# DRLGabarit.net
KiCad netlist of a schematic drawn in Altium Designer
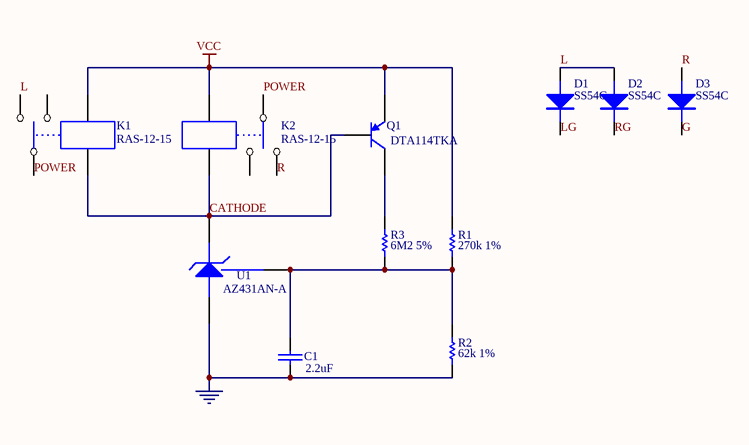
[diagram p0: DRLGabarit.SchDoc]

(export (version "E")
  (design (tool "Eeschema 10.0.6"))
  (components
    (comp (ref "C1")
      (value "2.2uF")
      (footprint "0805")
      (description "Capacitor")
      (libsource (lib "*") (part "CAP"))
    )
    (comp (ref "D1")
      (value "SS54C")
      (footprint "SMC")
      (description "Diode")
      (libsource (lib "Miscellaneous Devices") (part "DIODE"))
    )
    (comp (ref "D2")
      (value "SS54C")
      (footprint "SMC")
      (description "Diode")
      (libsource (lib "Miscellaneous Devices") (part "DIODE"))
    )
    (comp (ref "D3")
      (value "SS54C")
      (footprint "SMC")
      (description "Diode")
      (libsource (lib "Miscellaneous Devices") (part "DIODE"))
    )
    (comp (ref "K1")
      (value "RAS-12-15")
      (footprint "RELAY5PIN")
      (libsource (lib "Miscellaneous Devices") (part "RELAY-SPDT"))
    )
    (comp (ref "K2")
      (value "RAS-12-15")
      (footprint "RELAY5PIN")
      (libsource (lib "Miscellaneous Devices") (part "RELAY-SPDT"))
    )
    (comp (ref "Q1")
      (value "DTA114TKA")
      (footprint "sot-23")
      (description "PNP Bipolar Transistor")
      (fields
        (field (name "MANUFACTURER") "Generic Components")
        (field (name "PUBLISHER") "Altium Hobart Technology Centre")
      )
      (libsource (lib "Miscellaneous Devices") (part "PNP"))
    )
    (comp (ref "R1")
      (value "270k 1%")
      (footprint "0805")
      (description "Resistor")
      (fields
        (field (name "MANUFACTURER") "Generic Components")
        (field (name "PUBLISHER") "Altium Hobart Technology Centre")
      )
      (libsource (lib "Miscellaneous Devices") (part "Res1"))
    )
    (comp (ref "R2")
      (value "62k 1%")
      (footprint "0805")
      (description "Resistor")
      (fields
        (field (name "MANUFACTURER") "Generic Components")
        (field (name "PUBLISHER") "Altium Hobart Technology Centre")
      )
      (libsource (lib "Miscellaneous Devices") (part "Res1"))
    )
    (comp (ref "R3")
      (value "6M2 5%")
      (footprint "0805")
      (description "Resistor")
      (fields
        (field (name "MANUFACTURER") "Generic Components")
        (field (name "PUBLISHER") "Altium Hobart Technology Centre")
      )
      (libsource (lib "Miscellaneous Devices") (part "Res1"))
    )
    (comp (ref "U1") (value "AZ431AN-A") (footprint "SOT-23") (libsource (lib "Devices") (part "TL431")))
  )
  (nets
    (net (code "1") (name "/CATHODE") (class "Default")
      (node (ref "K1") (pin "4") (pinfunction "4_4") (pintype "passive"))
      (node (ref "K2") (pin "5") (pinfunction "5_5") (pintype "passive"))
      (node (ref "Q1") (pin "1") (pinfunction "B_1") (pintype "passive"))
      (node (ref "U1") (pin "3") (pinfunction "K_3") (pintype "passive"))
    )
    (net (code "2") (name "/G") (class "Default")
      (node (ref "D3") (pin "1") (pinfunction "K_1") (pintype "passive"))
    )
    (net (code "3") (name "/L") (class "Default")
      (node (ref "D1") (pin "2") (pinfunction "A_2") (pintype "passive"))
      (node (ref "D2") (pin "2") (pinfunction "A_2") (pintype "passive"))
      (node (ref "K1") (pin "2") (pinfunction "2_2") (pintype "passive"))
    )
    (net (code "4") (name "/LG") (class "Default")
      (node (ref "D1") (pin "1") (pinfunction "K_1") (pintype "passive"))
    )
    (net (code "5") (name "/POWER") (class "Default")
      (node (ref "K1") (pin "1") (pinfunction "1_1") (pintype "passive"))
      (node (ref "K2") (pin "1") (pinfunction "1_1") (pintype "passive"))
    )
    (net (code "6") (name "/R") (class "Default")
      (node (ref "D3") (pin "2") (pinfunction "A_2") (pintype "passive"))
      (node (ref "K2") (pin "2") (pinfunction "2_2") (pintype "passive"))
    )
    (net (code "7") (name "/RG") (class "Default")
      (node (ref "D2") (pin "1") (pinfunction "K_1") (pintype "passive"))
    )
    (net (code "8") (name "Net-(Q1-C)") (class "Default")
      (node (ref "Q1") (pin "2") (pinfunction "C_2") (pintype "passive"))
      (node (ref "R3") (pin "1") (pinfunction "1_1") (pintype "passive"))
    )
    (net (code "9") (name "Net-(U1-REF)") (class "Default")
      (node (ref "C1") (pin "1") (pinfunction "1_1") (pintype "passive"))
      (node (ref "R1") (pin "2") (pinfunction "2_2") (pintype "passive"))
      (node (ref "R2") (pin "1") (pinfunction "1_1") (pintype "passive"))
      (node (ref "R3") (pin "2") (pinfunction "2_2") (pintype "passive"))
      (node (ref "U1") (pin "1") (pinfunction "REF_1") (pintype "passive"))
    )
    (net (code "10") (name "PGND") (class "Default")
      (node (ref "C1") (pin "2") (pinfunction "2_2") (pintype "passive"))
      (node (ref "R2") (pin "2") (pinfunction "2_2") (pintype "passive"))
      (node (ref "U1") (pin "2") (pinfunction "A_2") (pintype "passive"))
    )
    (net (code "11") (name "VCC") (class "Default")
      (node (ref "K1") (pin "5") (pinfunction "5_5") (pintype "passive"))
      (node (ref "K2") (pin "4") (pinfunction "4_4") (pintype "passive"))
      (node (ref "Q1") (pin "3") (pinfunction "E_3") (pintype "passive"))
      (node (ref "R1") (pin "1") (pinfunction "1_1") (pintype "passive"))
    )
    (net (code "12") (name "unconnected-(K1-Pad3)") (class "Default")
      (node (ref "K1") (pin "3") (pinfunction "3_3") (pintype "passive"))
    )
    (net (code "13") (name "unconnected-(K2-Pad3)") (class "Default")
      (node (ref "K2") (pin "3") (pinfunction "3_3") (pintype "passive"))
    )
  )
)
